# stepper_simple.net
KiCad netlist of a schematic drawn in EAGLE
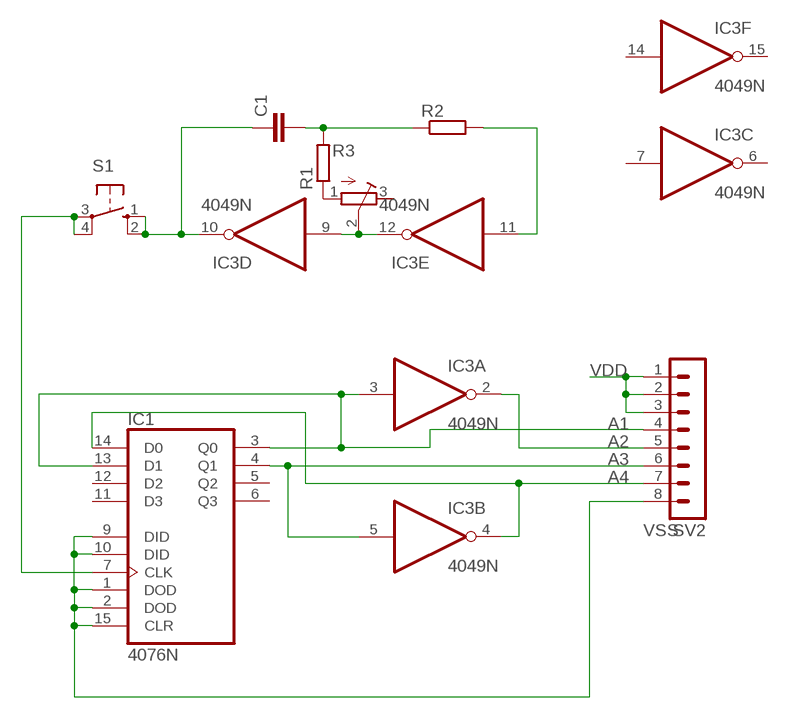
[diagram p0: schematic, sheet 1]

(export (version "E")
  (design (tool "Eeschema 10.0.6"))
  (components
    (comp (ref "C1")
      (value "C-EU050-024X044")
      (footprint "eagle-import:C050-024X044")
      (libsource (lib "eagle-import") (part "C-EU050-024X044"))
    )
    (comp (ref "IC1")
      (value "4076N")
      (footprint "eagle-import:DIL16")
      (libsource (lib "eagle-import") (part "4076N"))
    )
    (comp (ref "IC3")
      (value "4049N")
      (footprint "eagle-import:DIL16")
      (libsource (lib "eagle-import") (part "4049N"))
    )
    (comp (ref "R1")
      (value "R-EU_0207/10")
      (footprint "eagle-import:0207_10")
      (libsource (lib "eagle-import") (part "R-EU_0207/10"))
    )
    (comp (ref "R2")
      (value "R-EU_0207/10")
      (footprint "eagle-import:0207_10")
      (libsource (lib "eagle-import") (part "R-EU_0207/10"))
    )
    (comp (ref "R3")
      (value "R-TRIMM64W")
      (footprint "eagle-import:RTRIM64W")
      (libsource (lib "eagle-import") (part "R-TRIMM64W"))
    )
    (comp (ref "S1")
      (value "40-XX")
      (footprint "eagle-import:B3F-40XX")
      (fields (field (name "MF") "OMRON COMPONENTS USA") (field (name "MPN") "B3F-4000"))
      (libsource (lib "eagle-import") (part "40-XX"))
    )
    (comp (ref "SV2")
      (value "MA08-1")
      (footprint "eagle-import:MA08-1")
      (libsource (lib "eagle-import") (part "MA08-1"))
    )
  )
  (nets
    (net (code "1") (name "/A1") (class "Default")
      (node (ref "IC1") (pin "13") (pinfunction "D1_13") (pintype "input"))
      (node (ref "IC1") (pin "3") (pinfunction "Q0_3") (pintype "output"))
      (node (ref "IC3") (pin "3") (pinfunction "I_3") (pintype "input"))
      (node (ref "SV2") (pin "4") (pinfunction "4_4") (pintype "passive"))
    )
    (net (code "2") (name "/A2") (class "Default")
      (node (ref "IC3") (pin "2") (pinfunction "O_2") (pintype "output"))
      (node (ref "SV2") (pin "5") (pinfunction "5_5") (pintype "passive"))
    )
    (net (code "3") (name "/A3") (class "Default")
      (node (ref "IC1") (pin "4") (pinfunction "Q1_4") (pintype "output"))
      (node (ref "IC3") (pin "5") (pinfunction "I_5") (pintype "input"))
      (node (ref "SV2") (pin "6") (pinfunction "6_6") (pintype "passive"))
    )
    (net (code "4") (name "/A4") (class "Default")
      (node (ref "IC1") (pin "14") (pinfunction "D0_14") (pintype "input"))
      (node (ref "IC3") (pin "4") (pinfunction "O_4") (pintype "output"))
      (node (ref "SV2") (pin "7") (pinfunction "7_7") (pintype "passive"))
    )
    (net (code "5") (name "/VDD") (class "Default")
      (node (ref "SV2") (pin "1") (pinfunction "1_1") (pintype "passive"))
      (node (ref "SV2") (pin "2") (pinfunction "2_2") (pintype "passive"))
      (node (ref "SV2") (pin "3") (pinfunction "3_3") (pintype "passive"))
    )
    (net (code "6") (name "/VSS") (class "Default")
      (node (ref "IC1") (pin "1") (pinfunction "DOD_1") (pintype "input"))
      (node (ref "IC1") (pin "10") (pinfunction "DID_10") (pintype "input"))
      (node (ref "IC1") (pin "15") (pinfunction "CLR_15") (pintype "input"))
      (node (ref "IC1") (pin "2") (pinfunction "DOD_2") (pintype "input"))
      (node (ref "IC1") (pin "9") (pinfunction "DID_9") (pintype "input"))
      (node (ref "SV2") (pin "8") (pinfunction "8_8") (pintype "passive"))
    )
    (net (code "7") (name "Net-(C1-Pad2)") (class "Default")
      (node (ref "C1") (pin "2") (pinfunction "2_2") (pintype "passive"))
      (node (ref "R1") (pin "2") (pinfunction "2_2") (pintype "passive"))
      (node (ref "R2") (pin "1") (pinfunction "1_1") (pintype "passive"))
    )
    (net (code "8") (name "Net-(IC1A-CLK)") (class "Default")
      (node (ref "IC1") (pin "7") (pinfunction "CLK_7") (pintype "input"))
      (node (ref "S1") (pin "3") (pinfunction "P_3") (pintype "passive"))
      (node (ref "S1") (pin "4") (pinfunction "P1_4") (pintype "passive"))
    )
    (net (code "9") (name "Net-(IC3D-I)") (class "Default")
      (node (ref "IC3") (pin "12") (pinfunction "O_12") (pintype "output"))
      (node (ref "IC3") (pin "9") (pinfunction "I_9") (pintype "input"))
      (node (ref "R3") (pin "2") (pinfunction "S_2") (pintype "passive"))
    )
    (net (code "10") (name "Net-(IC3D-O)") (class "Default")
      (node (ref "C1") (pin "1") (pinfunction "1_1") (pintype "passive"))
      (node (ref "IC3") (pin "10") (pinfunction "O_10") (pintype "output"))
      (node (ref "S1") (pin "1") (pinfunction "S_1") (pintype "passive"))
      (node (ref "S1") (pin "2") (pinfunction "S1_2") (pintype "passive"))
    )
    (net (code "11") (name "Net-(IC3E-I)") (class "Default")
      (node (ref "IC3") (pin "11") (pinfunction "I_11") (pintype "input"))
      (node (ref "R2") (pin "2") (pinfunction "2_2") (pintype "passive"))
    )
    (net (code "12") (name "Net-(R3-A)") (class "Default")
      (node (ref "R1") (pin "1") (pinfunction "1_1") (pintype "passive"))
      (node (ref "R3") (pin "1") (pinfunction "A_1") (pintype "passive"))
    )
    (net (code "13") (name "unconnected-(IC1A-D2-Pad12)") (class "Default")
      (node (ref "IC1") (pin "12") (pinfunction "D2_12") (pintype "input"))
    )
    (net (code "14") (name "unconnected-(IC1A-D3-Pad11)") (class "Default")
      (node (ref "IC1") (pin "11") (pinfunction "D3_11") (pintype "input"))
    )
    (net (code "15") (name "unconnected-(IC1A-Q2-Pad5)") (class "Default")
      (node (ref "IC1") (pin "5") (pinfunction "Q2_5") (pintype "output"))
    )
    (net (code "16") (name "unconnected-(IC1A-Q3-Pad6)") (class "Default")
      (node (ref "IC1") (pin "6") (pinfunction "Q3_6") (pintype "output"))
    )
    (net (code "17") (name "unconnected-(IC3C-I-Pad7)") (class "Default")
      (node (ref "IC3") (pin "7") (pinfunction "I_7") (pintype "input"))
    )
    (net (code "18") (name "unconnected-(IC3C-O-Pad6)") (class "Default")
      (node (ref "IC3") (pin "6") (pinfunction "O_6") (pintype "output"))
    )
    (net (code "19") (name "unconnected-(IC3F-I-Pad14)") (class "Default")
      (node (ref "IC3") (pin "14") (pinfunction "I_14") (pintype "input"))
    )
    (net (code "20") (name "unconnected-(IC3F-O-Pad15)") (class "Default")
      (node (ref "IC3") (pin "15") (pinfunction "O_15") (pintype "output"))
    )
    (net (code "21") (name "unconnected-(R3-E-Pad3)") (class "Default")
      (node (ref "R3") (pin "3") (pinfunction "E_3") (pintype "passive"))
    )
  )
)
